# v001.net
KiCad netlist of a schematic drawn in EAGLE
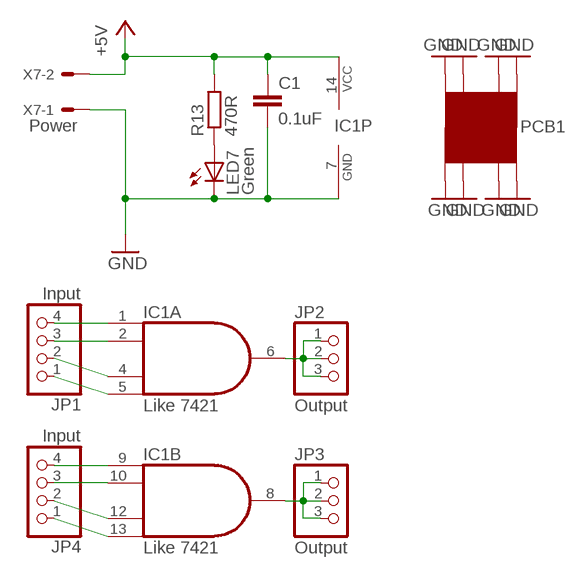
[diagram p0: schematic, sheet 1]

(export (version "E")
  (design (tool "Eeschema 10.0.6"))
  (components
    (comp (ref "C1")
      (value "0.1uF")
      (footprint "eagle-import:C050-024X044")
      (libsource (lib "eagle-import") (part "C-EU050-024X044"))
    )
    (comp (ref "IC1")
      (value "Like 7421")
      (footprint "eagle-import:DIL14")
      (libsource (lib "eagle-import") (part "7421NALS"))
    )
    (comp (ref "JP1")
      (value "Input")
      (footprint "eagle-import:1X04")
      (libsource (lib "eagle-import") (part "PINHD-1X4"))
    )
    (comp (ref "JP2")
      (value "Output")
      (footprint "eagle-import:1X03")
      (libsource (lib "eagle-import") (part "PINHD-1X3"))
    )
    (comp (ref "JP3")
      (value "Output")
      (footprint "eagle-import:1X03")
      (libsource (lib "eagle-import") (part "PINHD-1X3"))
    )
    (comp (ref "JP4")
      (value "Input")
      (footprint "eagle-import:1X04")
      (libsource (lib "eagle-import") (part "PINHD-1X4"))
    )
    (comp (ref "LED7")
      (value "Green")
      (footprint "eagle-import:LED3MM")
      (libsource (lib "eagle-import") (part "LED3MM"))
    )
    (comp (ref "PCB1")
      (value "PCB05X05")
      (footprint "eagle-import:PCB_05X05")
      (libsource (lib "eagle-import") (part "PCB05X05"))
    )
    (comp (ref "R13")
      (value "470R")
      (footprint "eagle-import:0204_7")
      (libsource (lib "eagle-import") (part "R-EU_0204/7"))
    )
    (comp (ref "X7")
      (value "Power")
      (footprint "eagle-import:6410-02")
      (libsource (lib "eagle-import") (part "22-?-0227-2021"))
    )
  )
  (nets
    (net (code "1") (name "+5V") (class "Default")
      (node (ref "C1") (pin "1") (pinfunction "1_1") (pintype "passive"))
      (node (ref "IC1") (pin "14") (pinfunction "VCC_14") (pintype "power_in"))
      (node (ref "R13") (pin "2") (pinfunction "2_2") (pintype "passive"))
      (node (ref "X7") (pin "2") (pinfunction "S_2") (pintype "passive"))
    )
    (net (code "2") (name "GND") (class "Default")
      (node (ref "C1") (pin "2") (pinfunction "2_2") (pintype "passive"))
      (node (ref "IC1") (pin "7") (pinfunction "GND_7") (pintype "power_in"))
      (node (ref "LED7") (pin "K") (pinfunction "C_K") (pintype "passive"))
      (node (ref "PCB1") (pin "GND@1") (pinfunction "GND_GND@1") (pintype "bidirectional"))
      (node (ref "PCB1") (pin "GND@2") (pinfunction "GND_GND@2") (pintype "bidirectional"))
      (node (ref "PCB1") (pin "GND@3") (pinfunction "GND_GND@3") (pintype "bidirectional"))
      (node (ref "PCB1") (pin "GND@4") (pinfunction "GND_GND@4") (pintype "bidirectional"))
      (node (ref "PCB1") (pin "GND@5") (pinfunction "GND_GND@5") (pintype "bidirectional"))
      (node (ref "PCB1") (pin "GND@6") (pinfunction "GND_GND@6") (pintype "bidirectional"))
      (node (ref "PCB1") (pin "GND@7") (pinfunction "GND_GND@7") (pintype "bidirectional"))
      (node (ref "PCB1") (pin "GND@8") (pinfunction "GND_GND@8") (pintype "bidirectional"))
      (node (ref "X7") (pin "1") (pinfunction "S_1") (pintype "passive"))
    )
    (net (code "3") (name "Net-(IC1A-I0)") (class "Default")
      (node (ref "IC1") (pin "1") (pinfunction "I0_1") (pintype "input"))
      (node (ref "JP1") (pin "4") (pinfunction "4_4") (pintype "passive"))
    )
    (net (code "4") (name "Net-(IC1A-I1)") (class "Default")
      (node (ref "IC1") (pin "2") (pinfunction "I1_2") (pintype "input"))
      (node (ref "JP1") (pin "3") (pinfunction "3_3") (pintype "passive"))
    )
    (net (code "5") (name "Net-(IC1A-I2)") (class "Default")
      (node (ref "IC1") (pin "4") (pinfunction "I2_4") (pintype "input"))
      (node (ref "JP1") (pin "2") (pinfunction "2_2") (pintype "passive"))
    )
    (net (code "6") (name "Net-(IC1A-I3)") (class "Default")
      (node (ref "IC1") (pin "5") (pinfunction "I3_5") (pintype "input"))
      (node (ref "JP1") (pin "1") (pinfunction "1_1") (pintype "passive"))
    )
    (net (code "7") (name "Net-(IC1A-O)") (class "Default")
      (node (ref "IC1") (pin "6") (pinfunction "O_6") (pintype "output"))
      (node (ref "JP2") (pin "1") (pinfunction "1_1") (pintype "passive"))
      (node (ref "JP2") (pin "2") (pinfunction "2_2") (pintype "passive"))
      (node (ref "JP2") (pin "3") (pinfunction "3_3") (pintype "passive"))
    )
    (net (code "8") (name "Net-(IC1B-I0)") (class "Default")
      (node (ref "IC1") (pin "9") (pinfunction "I0_9") (pintype "input"))
      (node (ref "JP4") (pin "4") (pinfunction "4_4") (pintype "passive"))
    )
    (net (code "9") (name "Net-(IC1B-I1)") (class "Default")
      (node (ref "IC1") (pin "10") (pinfunction "I1_10") (pintype "input"))
      (node (ref "JP4") (pin "3") (pinfunction "3_3") (pintype "passive"))
    )
    (net (code "10") (name "Net-(IC1B-I2)") (class "Default")
      (node (ref "IC1") (pin "12") (pinfunction "I2_12") (pintype "input"))
      (node (ref "JP4") (pin "2") (pinfunction "2_2") (pintype "passive"))
    )
    (net (code "11") (name "Net-(IC1B-I3)") (class "Default")
      (node (ref "IC1") (pin "13") (pinfunction "I3_13") (pintype "input"))
      (node (ref "JP4") (pin "1") (pinfunction "1_1") (pintype "passive"))
    )
    (net (code "12") (name "Net-(IC1B-O)") (class "Default")
      (node (ref "IC1") (pin "8") (pinfunction "O_8") (pintype "output"))
      (node (ref "JP3") (pin "1") (pinfunction "1_1") (pintype "passive"))
      (node (ref "JP3") (pin "2") (pinfunction "2_2") (pintype "passive"))
      (node (ref "JP3") (pin "3") (pinfunction "3_3") (pintype "passive"))
    )
    (net (code "13") (name "Net-(LED7-PadA)") (class "Default")
      (node (ref "LED7") (pin "A") (pinfunction "A_A") (pintype "passive"))
      (node (ref "R13") (pin "1") (pinfunction "1_1") (pintype "passive"))
    )
  )
)
